# current-sense_resistor.net
KiCad netlist of a schematic drawn in EAGLE
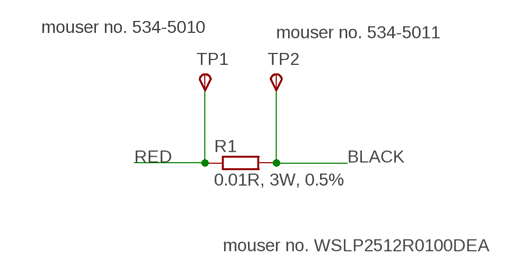
[diagram p0: schematic, sheet 1]

(export (version "E")
  (design (tool "Eeschema 10.0.6"))
  (components
    (comp (ref "R1")
      (value "0.01R, 3W, 0.5%")
      (footprint "eagle-import:R2512")
      (libsource (lib "eagle-import") (part "R-EU_R2512"))
    )
    (comp (ref "TP1")
      (value "534-5011")
      (footprint "eagle-import:P1-20")
      (libsource (lib "eagle-import") (part "TPSPAD1-20"))
    )
    (comp (ref "TP2")
      (value "534-5010")
      (footprint "eagle-import:P1-20")
      (libsource (lib "eagle-import") (part "TPSPAD1-20"))
    )
  )
  (nets
    (net (code "1") (name "/BLACK") (class "Default")
      (node (ref "R1") (pin "2") (pinfunction "2_2") (pintype "passive"))
      (node (ref "TP2") (pin "TP") (pinfunction "PP_TP") (pintype "input"))
    )
    (net (code "2") (name "/RED") (class "Default")
      (node (ref "R1") (pin "1") (pinfunction "1_1") (pintype "passive"))
      (node (ref "TP1") (pin "TP") (pinfunction "PP_TP") (pintype "input"))
    )
  )
)
